# 3v3BuckConverterTPS62056.net
KiCad netlist of a schematic drawn in Altium Designer
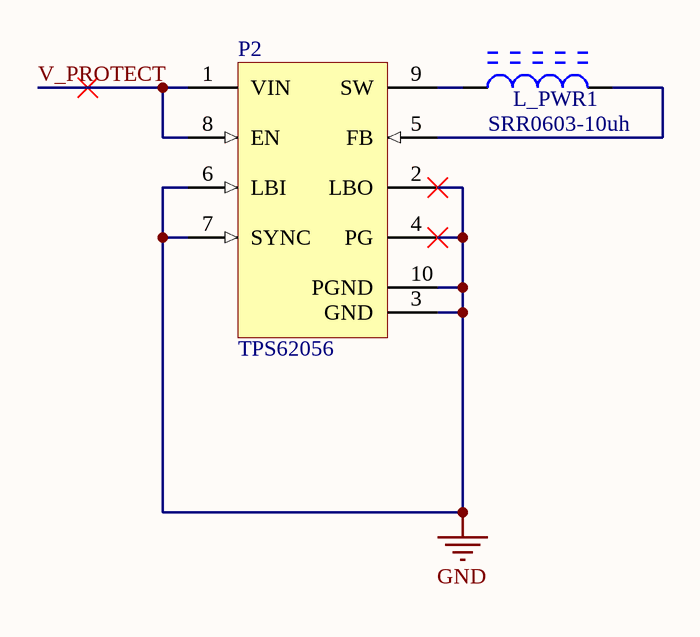
[diagram p0: 3v3BuckConverterTPS62056.SchDoc]

(export (version "E")
  (design (tool "Eeschema 10.0.6"))
  (components
    (comp (ref "L_PWR1")
      (value "SRR0603-10uh")
      (footprint "BOUR-SRR0603_V")
      (description "Shielded Power Inductor, 10 uH, +/- 20%, -40 to 125 degC, 2-Pin SMD, RoHS, Tape and Reel")
      (fields (field (name "MANUFACTURER") "Bourns") (field (name "TOLERANCE") "±20%"))
      (libsource (lib "Altium Content Vault") (part "IND-FERR-2"))
    )
    (comp (ref "P2")
      (value "TPS62056")
      (footprint "DGS10_L")
      (fields (field (name "MANUFACTURER") "Texas Instruments") (field (name "PARTNUMBER") "TPS62056DGSRG4"))
      (libsource (lib "Altium Content Vault") (part "TI-TPS62056DGS10"))
    )
  )
  (nets
    (net (code "1") (name "/V_PROTECT") (class "Default")
      (node (ref "P2") (pin "1") (pinfunction "VIN_1") (pintype "power_in"))
      (node (ref "P2") (pin "8") (pinfunction "EN_8") (pintype "input"))
    )
    (net (code "2") (name "GND") (class "Default")
      (node (ref "P2") (pin "10") (pinfunction "PGND_10") (pintype "power_in"))
      (node (ref "P2") (pin "2") (pinfunction "LBO_2") (pintype "tri_state"))
      (node (ref "P2") (pin "3") (pinfunction "GND_3") (pintype "power_in"))
      (node (ref "P2") (pin "4") (pinfunction "PG_4") (pintype "open_collector"))
      (node (ref "P2") (pin "6") (pinfunction "LBI_6") (pintype "input"))
      (node (ref "P2") (pin "7") (pinfunction "SYNC_7") (pintype "input"))
    )
    (net (code "3") (name "Net-(P2-FB)") (class "Default")
      (node (ref "L_PWR1") (pin "2") (pinfunction "2_2") (pintype "passive"))
      (node (ref "P2") (pin "5") (pinfunction "FB_5") (pintype "input"))
    )
    (net (code "4") (name "Net-(P2-SW)") (class "Default")
      (node (ref "L_PWR1") (pin "1") (pinfunction "1_1") (pintype "passive"))
      (node (ref "P2") (pin "9") (pinfunction "SW_9") (pintype "power_in"))
    )
  )
)
